# Wiper_Control_v3.net
KiCad netlist of a schematic drawn in EAGLE
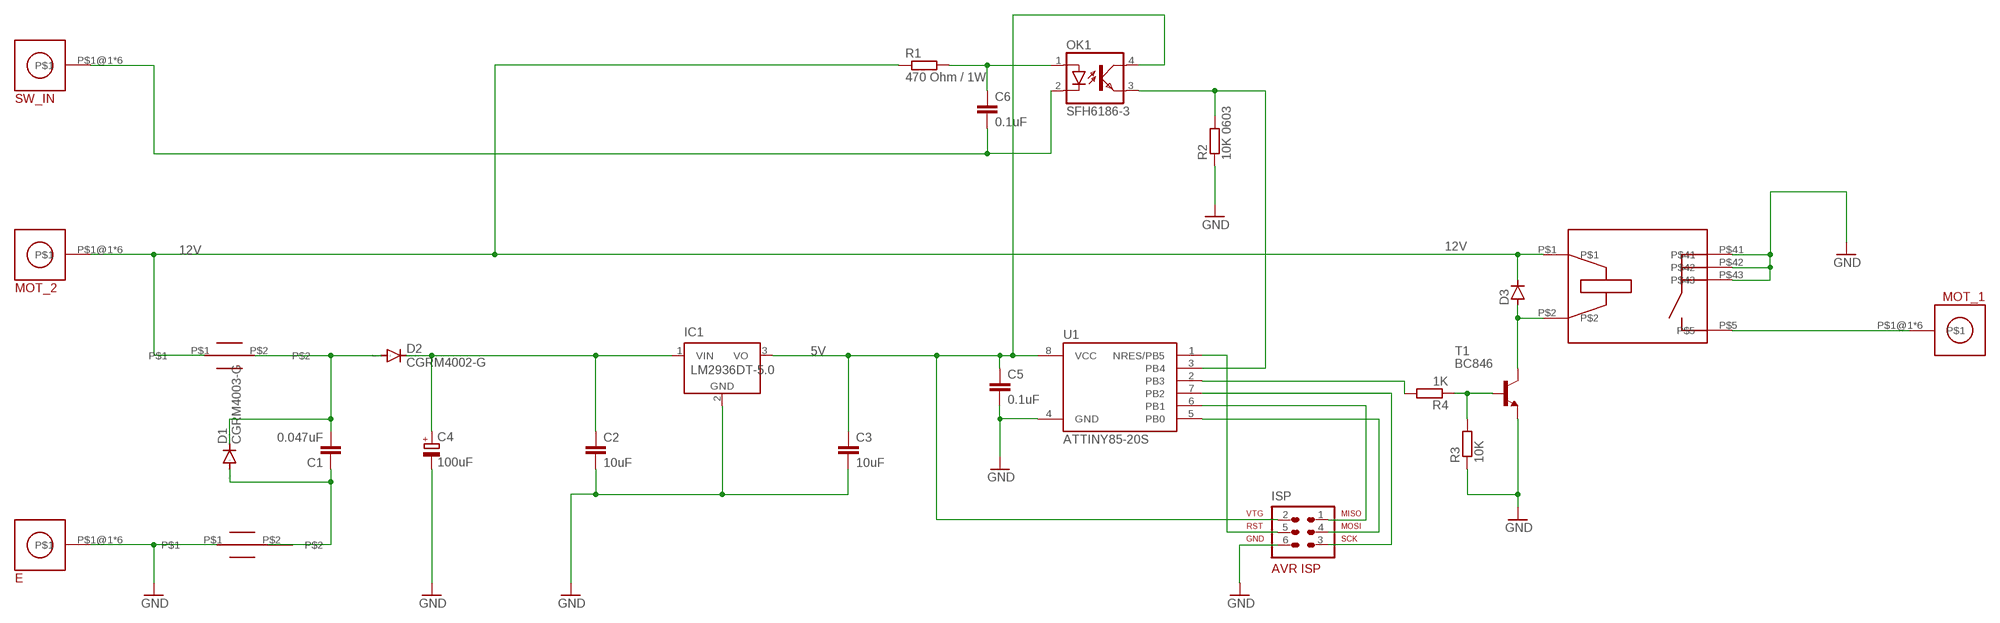
[diagram p0: schematic, sheet 1]

(export (version "E")
  (design (tool "Eeschema 10.0.6"))
  (components
    (comp (ref "B1")
      (value "FBMJ2125")
      (footprint "eagle-import:FBMJ")
      (libsource (lib "eagle-import") (part "FBMJ2125"))
    )
    (comp (ref "B2")
      (value "FBMJ2125")
      (footprint "eagle-import:FBMJ")
      (libsource (lib "eagle-import") (part "FBMJ2125"))
    )
    (comp (ref "C1")
      (value "0.047uF")
      (footprint "eagle-import:C0603")
      (libsource (lib "eagle-import") (part "C-EUC0603"))
    )
    (comp (ref "C2")
      (value "10uF")
      (footprint "eagle-import:C0805")
      (libsource (lib "eagle-import") (part "C-EUC0805"))
    )
    (comp (ref "C3")
      (value "10uF")
      (footprint "eagle-import:C0805")
      (libsource (lib "eagle-import") (part "C-EUC0805"))
    )
    (comp (ref "C4")
      (value "100uF")
      (footprint "eagle-import:E2,5-7")
      (libsource (lib "eagle-import") (part "CPOL-EUE2.5-7"))
    )
    (comp (ref "C5")
      (value "0.1uF")
      (footprint "eagle-import:C0603")
      (libsource (lib "eagle-import") (part "C-EUC0603"))
    )
    (comp (ref "C6")
      (value "0.1uF")
      (footprint "eagle-import:C0603")
      (libsource (lib "eagle-import") (part "C-EUC0603"))
    )
    (comp (ref "D1")
      (value "CGRM4003-G")
      (footprint "eagle-import:SOD-123_MINI-SMA")
      (libsource (lib "eagle-import") (part "CGRM400-G3"))
    )
    (comp (ref "D2")
      (value "CGRM4002-G")
      (footprint "eagle-import:SOD-123_MINI-SMA")
      (libsource (lib "eagle-import") (part "CGRM400-G2"))
    )
    (comp (ref "D3")
      (value "D-SOD123")
      (footprint "eagle-import:SOD123")
      (libsource (lib "eagle-import") (part "D-SOD123"))
    )
    (comp (ref "E")
      (value "M4_SCREW_TERMINAL")
      (footprint "eagle-import:M4_SCREW_TERMINAL")
      (libsource (lib "eagle-import") (part "M4_SCREW_TERMINAL"))
    )
    (comp (ref "IC1")
      (value "LM2936DT-5.0")
      (footprint "eagle-import:TO252")
      (fields (field (name "MF") "NATIONAL SEMICONDUCTOR") (field (name "MPN") "LM2936DT-5.0/NOPB"))
      (libsource (lib "eagle-import") (part "LM2936?DT-5.0"))
    )
    (comp (ref "ISP")
      (value "AVR-ISP-6")
      (footprint "eagle-import:AVR-ISP-6")
      (libsource (lib "eagle-import") (part "AVR-ISP-6"))
    )
    (comp (ref "MOT_1")
      (value "M4_SCREW_TERMINAL")
      (footprint "eagle-import:M4_SCREW_TERMINAL")
      (libsource (lib "eagle-import") (part "M4_SCREW_TERMINAL"))
    )
    (comp (ref "MOT_2")
      (value "M4_SCREW_TERMINAL")
      (footprint "eagle-import:M4_SCREW_TERMINAL")
      (libsource (lib "eagle-import") (part "M4_SCREW_TERMINAL"))
    )
    (comp (ref "OK1")
      (value "SFH6186-3")
      (footprint "eagle-import:SMD4-7")
      (fields (field (name "MF") "VISHAY/TELEFUNKEN"))
      (libsource (lib "eagle-import") (part "SFH618?6-3"))
    )
    (comp (ref "R1")
      (value "470 Ohm / 1W")
      (footprint "eagle-import:R2512")
      (libsource (lib "eagle-import") (part "R-EU_R2512"))
    )
    (comp (ref "R2")
      (value "10K 0603")
      (footprint "eagle-import:R0603")
      (libsource (lib "eagle-import") (part "R-EU_R0603"))
    )
    (comp (ref "R3")
      (value "10K")
      (footprint "eagle-import:R0603")
      (libsource (lib "eagle-import") (part "R-EU_R0603"))
    )
    (comp (ref "R4")
      (value "1K")
      (footprint "eagle-import:R0603")
      (libsource (lib "eagle-import") (part "R-EU_R0603"))
    )
    (comp (ref "SW_IN")
      (value "M4_SCREW_TERMINAL")
      (footprint "eagle-import:M4_SCREW_TERMINAL")
      (libsource (lib "eagle-import") (part "M4_SCREW_TERMINAL"))
    )
    (comp (ref "T1")
      (value "BC846")
      (footprint "eagle-import:SOT23")
      (libsource (lib "eagle-import") (part "BC846"))
    )
    (comp (ref "U$3")
      (value "RELAY")
      (footprint "eagle-import:RELAY")
      (libsource (lib "eagle-import") (part "RELAY"))
    )
    (comp (ref "U1")
      (value "ATTINY85-20S")
      (footprint "eagle-import:SOIC8_EIAJ_208MIL")
      (libsource (lib "eagle-import") (part "ATTINY85S-20"))
    )
  )
  (nets
    (net (code "1") (name "/5V") (class "Default")
      (node (ref "C3") (pin "1") (pinfunction "1_1") (pintype "passive"))
      (node (ref "C5") (pin "1") (pinfunction "1_1") (pintype "passive"))
      (node (ref "IC1") (pin "3") (pinfunction "VO_3") (pintype "passive"))
      (node (ref "ISP") (pin "2") (pinfunction "2_2") (pintype "passive"))
      (node (ref "OK1") (pin "4") (pinfunction "COL_4") (pintype "passive"))
      (node (ref "U1") (pin "8") (pinfunction "VCC_8") (pintype "power_in"))
    )
    (net (code "2") (name "/12V") (class "Default")
      (node (ref "B1") (pin "P$1") (pinfunction "P$1_P$1") (pintype "bidirectional"))
      (node (ref "D3") (pin "1") (pinfunction "C_1") (pintype "passive"))
      (node (ref "MOT_2") (pin "P$1@1") (pinfunction "P$1_P$1@1") (pintype "bidirectional"))
      (node (ref "MOT_2") (pin "P$1@2") (pinfunction "P$1_P$1@2") (pintype "bidirectional"))
      (node (ref "MOT_2") (pin "P$1@3") (pinfunction "P$1_P$1@3") (pintype "bidirectional"))
      (node (ref "MOT_2") (pin "P$1@4") (pinfunction "P$1_P$1@4") (pintype "bidirectional"))
      (node (ref "MOT_2") (pin "P$1@5") (pinfunction "P$1_P$1@5") (pintype "bidirectional"))
      (node (ref "MOT_2") (pin "P$1@6") (pinfunction "P$1_P$1@6") (pintype "bidirectional"))
      (node (ref "R1") (pin "1") (pinfunction "1_1") (pintype "passive"))
      (node (ref "U$3") (pin "P$1") (pinfunction "P$1_P$1") (pintype "bidirectional"))
    )
    (net (code "3") (name "GND") (class "Default")
      (node (ref "B2") (pin "P$1") (pinfunction "P$1_P$1") (pintype "bidirectional"))
      (node (ref "C2") (pin "2") (pinfunction "2_2") (pintype "passive"))
      (node (ref "C3") (pin "2") (pinfunction "2_2") (pintype "passive"))
      (node (ref "C4") (pin "-") (pinfunction "-_-") (pintype "passive"))
      (node (ref "C5") (pin "2") (pinfunction "2_2") (pintype "passive"))
      (node (ref "E") (pin "P$1@1") (pinfunction "P$1_P$1@1") (pintype "bidirectional"))
      (node (ref "E") (pin "P$1@2") (pinfunction "P$1_P$1@2") (pintype "bidirectional"))
      (node (ref "E") (pin "P$1@3") (pinfunction "P$1_P$1@3") (pintype "bidirectional"))
      (node (ref "E") (pin "P$1@4") (pinfunction "P$1_P$1@4") (pintype "bidirectional"))
      (node (ref "E") (pin "P$1@5") (pinfunction "P$1_P$1@5") (pintype "bidirectional"))
      (node (ref "E") (pin "P$1@6") (pinfunction "P$1_P$1@6") (pintype "bidirectional"))
      (node (ref "IC1") (pin "2") (pinfunction "GND_2") (pintype "passive"))
      (node (ref "ISP") (pin "6") (pinfunction "6_6") (pintype "passive"))
      (node (ref "R2") (pin "1") (pinfunction "1_1") (pintype "passive"))
      (node (ref "R3") (pin "1") (pinfunction "1_1") (pintype "passive"))
      (node (ref "T1") (pin "2") (pinfunction "E_2") (pintype "passive"))
      (node (ref "U$3") (pin "P$41") (pinfunction "P$41_P$41") (pintype "bidirectional"))
      (node (ref "U$3") (pin "P$42") (pinfunction "P$42_P$42") (pintype "bidirectional"))
      (node (ref "U$3") (pin "P$43") (pinfunction "P$43_P$43") (pintype "bidirectional"))
      (node (ref "U1") (pin "4") (pinfunction "GND_4") (pintype "power_in"))
    )
    (net (code "4") (name "Net-(B1-PadP$2)") (class "Default")
      (node (ref "B1") (pin "P$2") (pinfunction "P$2_P$2") (pintype "bidirectional"))
      (node (ref "C1") (pin "2") (pinfunction "2_2") (pintype "passive"))
      (node (ref "D1") (pin "C") (pinfunction "C_C") (pintype "passive"))
      (node (ref "D2") (pin "A") (pinfunction "A_A") (pintype "passive"))
    )
    (net (code "5") (name "Net-(B2-PadP$2)") (class "Default")
      (node (ref "B2") (pin "P$2") (pinfunction "P$2_P$2") (pintype "bidirectional"))
      (node (ref "C1") (pin "1") (pinfunction "1_1") (pintype "passive"))
      (node (ref "D1") (pin "A") (pinfunction "A_A") (pintype "passive"))
    )
    (net (code "6") (name "Net-(D3-A)") (class "Default")
      (node (ref "D3") (pin "2") (pinfunction "A_2") (pintype "passive"))
      (node (ref "T1") (pin "3") (pinfunction "C_3") (pintype "passive"))
      (node (ref "U$3") (pin "P$2") (pinfunction "P$2_P$2") (pintype "bidirectional"))
    )
    (net (code "7") (name "Net-(IC1-VIN)") (class "Default")
      (node (ref "C2") (pin "1") (pinfunction "1_1") (pintype "passive"))
      (node (ref "C4") (pin "+") (pinfunction "+_+") (pintype "passive"))
      (node (ref "D2") (pin "C") (pinfunction "C_C") (pintype "passive"))
      (node (ref "IC1") (pin "1") (pinfunction "VIN_1") (pintype "input"))
    )
    (net (code "8") (name "Net-(MOT_1-P$1-PadP$1@1)") (class "Default")
      (node (ref "MOT_1") (pin "P$1@1") (pinfunction "P$1_P$1@1") (pintype "bidirectional"))
      (node (ref "MOT_1") (pin "P$1@2") (pinfunction "P$1_P$1@2") (pintype "bidirectional"))
      (node (ref "MOT_1") (pin "P$1@3") (pinfunction "P$1_P$1@3") (pintype "bidirectional"))
      (node (ref "MOT_1") (pin "P$1@4") (pinfunction "P$1_P$1@4") (pintype "bidirectional"))
      (node (ref "MOT_1") (pin "P$1@5") (pinfunction "P$1_P$1@5") (pintype "bidirectional"))
      (node (ref "MOT_1") (pin "P$1@6") (pinfunction "P$1_P$1@6") (pintype "bidirectional"))
      (node (ref "U$3") (pin "P$5") (pinfunction "P$5_P$5") (pintype "bidirectional"))
    )
    (net (code "9") (name "Net-(OK1-A)") (class "Default")
      (node (ref "C6") (pin "1") (pinfunction "1_1") (pintype "passive"))
      (node (ref "OK1") (pin "1") (pinfunction "A_1") (pintype "passive"))
      (node (ref "R1") (pin "2") (pinfunction "2_2") (pintype "passive"))
    )
    (net (code "10") (name "Net-(OK1-C)") (class "Default")
      (node (ref "C6") (pin "2") (pinfunction "2_2") (pintype "passive"))
      (node (ref "OK1") (pin "2") (pinfunction "C_2") (pintype "passive"))
      (node (ref "SW_IN") (pin "P$1@1") (pinfunction "P$1_P$1@1") (pintype "bidirectional"))
      (node (ref "SW_IN") (pin "P$1@2") (pinfunction "P$1_P$1@2") (pintype "bidirectional"))
      (node (ref "SW_IN") (pin "P$1@3") (pinfunction "P$1_P$1@3") (pintype "bidirectional"))
      (node (ref "SW_IN") (pin "P$1@4") (pinfunction "P$1_P$1@4") (pintype "bidirectional"))
      (node (ref "SW_IN") (pin "P$1@5") (pinfunction "P$1_P$1@5") (pintype "bidirectional"))
      (node (ref "SW_IN") (pin "P$1@6") (pinfunction "P$1_P$1@6") (pintype "bidirectional"))
    )
    (net (code "11") (name "Net-(OK1-EMIT)") (class "Default")
      (node (ref "OK1") (pin "3") (pinfunction "EMIT_3") (pintype "passive"))
      (node (ref "R2") (pin "2") (pinfunction "2_2") (pintype "passive"))
      (node (ref "U1") (pin "3") (pinfunction "PB4_3") (pintype "bidirectional"))
    )
    (net (code "12") (name "Net-(T1-B)") (class "Default")
      (node (ref "R3") (pin "2") (pinfunction "2_2") (pintype "passive"))
      (node (ref "R4") (pin "1") (pinfunction "1_1") (pintype "passive"))
      (node (ref "T1") (pin "1") (pinfunction "B_1") (pintype "passive"))
    )
    (net (code "13") (name "Net-(U1-NRES{slash}PB5)") (class "Default")
      (node (ref "ISP") (pin "5") (pinfunction "5_5") (pintype "passive"))
      (node (ref "U1") (pin "1") (pinfunction "NRES/PB5_1") (pintype "bidirectional"))
    )
    (net (code "14") (name "Net-(U1-PB0)") (class "Default")
      (node (ref "ISP") (pin "4") (pinfunction "4_4") (pintype "passive"))
      (node (ref "U1") (pin "5") (pinfunction "PB0_5") (pintype "bidirectional"))
    )
    (net (code "15") (name "Net-(U1-PB1)") (class "Default")
      (node (ref "ISP") (pin "1") (pinfunction "1_1") (pintype "passive"))
      (node (ref "U1") (pin "6") (pinfunction "PB1_6") (pintype "bidirectional"))
    )
    (net (code "16") (name "Net-(U1-PB2)") (class "Default")
      (node (ref "ISP") (pin "3") (pinfunction "3_3") (pintype "passive"))
      (node (ref "U1") (pin "7") (pinfunction "PB2_7") (pintype "bidirectional"))
    )
    (net (code "17") (name "Net-(U1-PB3)") (class "Default")
      (node (ref "R4") (pin "2") (pinfunction "2_2") (pintype "passive"))
      (node (ref "U1") (pin "2") (pinfunction "PB3_2") (pintype "bidirectional"))
    )
  )
)
